# SwitchFeather.net
KiCad netlist of a schematic drawn in EAGLE
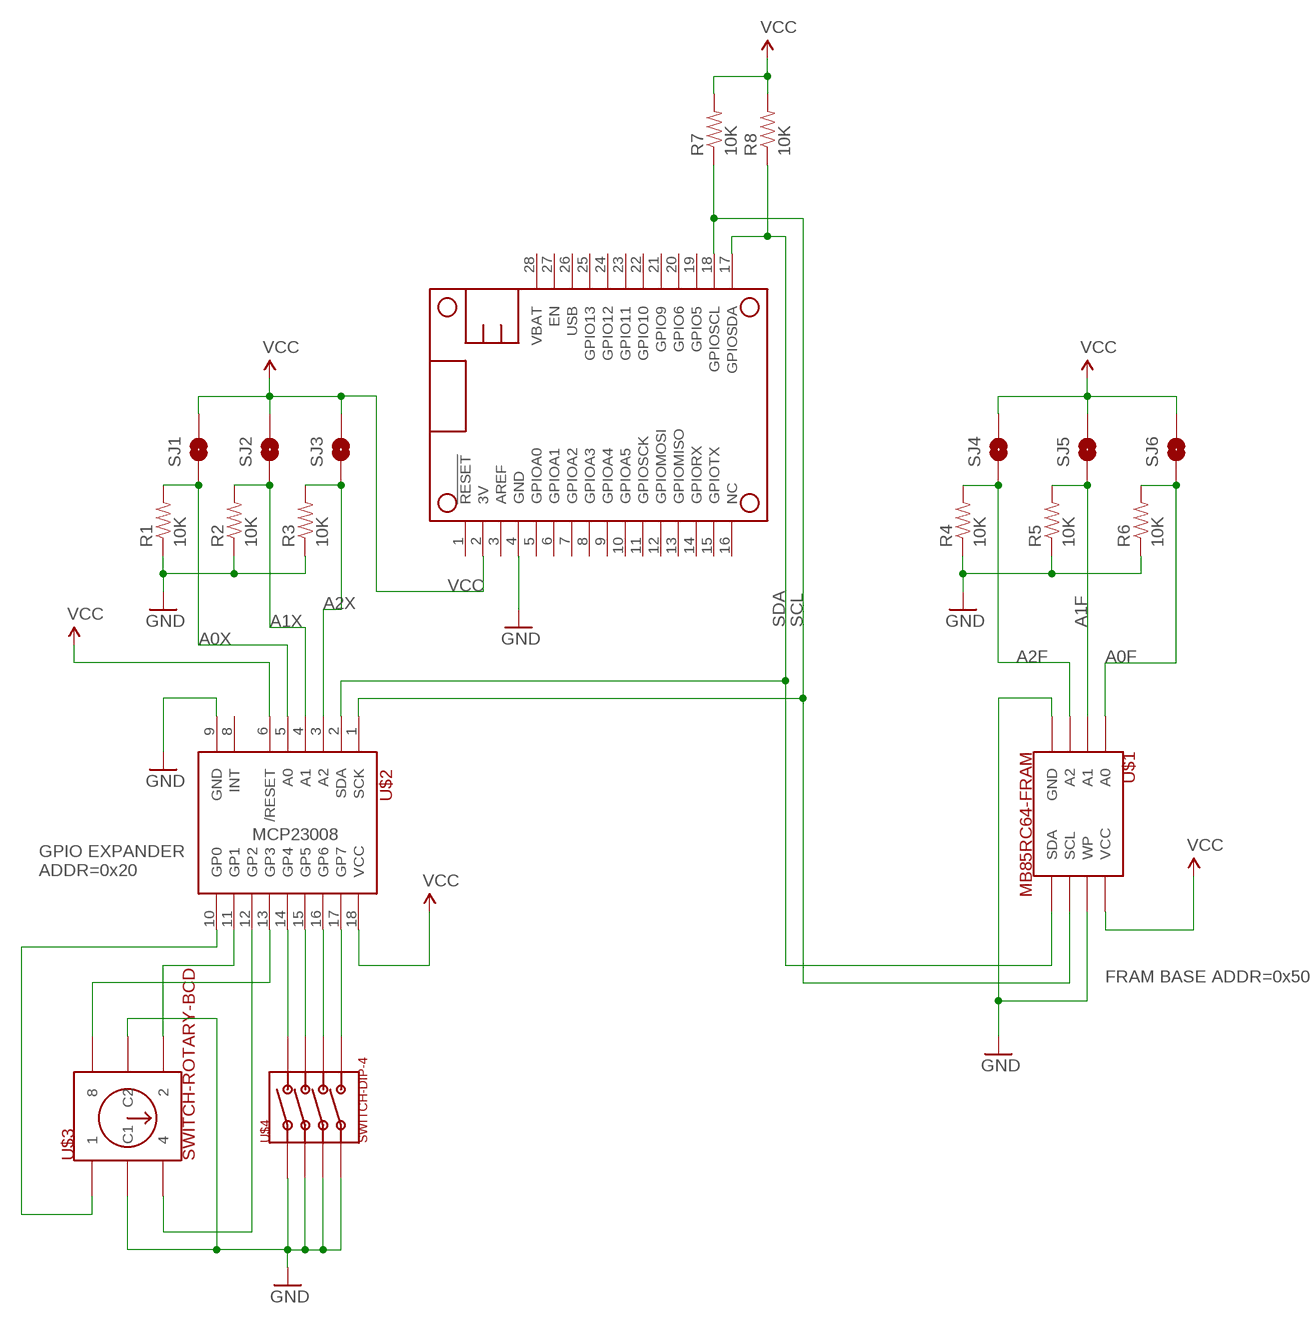
[diagram p0: schematic, sheet 1]

(export (version "E")
  (design (tool "Eeschema 10.0.6"))
  (components
    (comp (ref "MS1")
      (value "FEATHERWING")
      (footprint "eagle-import:FEATHERWING")
      (libsource (lib "eagle-import") (part "FEATHERWING"))
    )
    (comp (ref "R1")
      (value "10K")
      (footprint "eagle-import:0603-RES")
      (libsource (lib "eagle-import") (part "RES-10K-06030603"))
    )
    (comp (ref "R2")
      (value "10K")
      (footprint "eagle-import:0603-RES")
      (libsource (lib "eagle-import") (part "RES-10K-06030603"))
    )
    (comp (ref "R3")
      (value "10K")
      (footprint "eagle-import:0603-RES")
      (libsource (lib "eagle-import") (part "RES-10K-06030603"))
    )
    (comp (ref "R4")
      (value "10K")
      (footprint "eagle-import:0603-RES")
      (libsource (lib "eagle-import") (part "RES-10K-06030603"))
    )
    (comp (ref "R5")
      (value "10K")
      (footprint "eagle-import:0603-RES")
      (libsource (lib "eagle-import") (part "RES-10K-06030603"))
    )
    (comp (ref "R6")
      (value "10K")
      (footprint "eagle-import:0603-RES")
      (libsource (lib "eagle-import") (part "RES-10K-06030603"))
    )
    (comp (ref "R7")
      (value "10K")
      (footprint "eagle-import:0603-RES")
      (libsource (lib "eagle-import") (part "RES-10K-06030603"))
    )
    (comp (ref "R8")
      (value "10K")
      (footprint "eagle-import:0603-RES")
      (libsource (lib "eagle-import") (part "RES-10K-06030603"))
    )
    (comp (ref "SJ1")
      (value "JUMPER-PAD-2-NO")
      (footprint "eagle-import:PAD-JUMPER-2-NO_NO_SILK")
      (libsource (lib "eagle-import") (part "JUMPER-PAD-2-NO"))
    )
    (comp (ref "SJ2")
      (value "JUMPER-PAD-2-NO")
      (footprint "eagle-import:PAD-JUMPER-2-NO_NO_SILK")
      (libsource (lib "eagle-import") (part "JUMPER-PAD-2-NO"))
    )
    (comp (ref "SJ3")
      (value "JUMPER-PAD-2-NO")
      (footprint "eagle-import:PAD-JUMPER-2-NO_NO_SILK")
      (libsource (lib "eagle-import") (part "JUMPER-PAD-2-NO"))
    )
    (comp (ref "SJ4")
      (value "JUMPER-PAD-2-NO")
      (footprint "eagle-import:PAD-JUMPER-2-NO_NO_SILK")
      (libsource (lib "eagle-import") (part "JUMPER-PAD-2-NO"))
    )
    (comp (ref "SJ5")
      (value "JUMPER-PAD-2-NO")
      (footprint "eagle-import:PAD-JUMPER-2-NO_NO_SILK")
      (libsource (lib "eagle-import") (part "JUMPER-PAD-2-NO"))
    )
    (comp (ref "SJ6")
      (value "JUMPER-PAD-2-NO")
      (footprint "eagle-import:PAD-JUMPER-2-NO_NO_SILK")
      (libsource (lib "eagle-import") (part "JUMPER-PAD-2-NO"))
    )
    (comp (ref "U$1")
      (value "MB85RC64-FRAM")
      (footprint "eagle-import:8-SOIC-MAXIM")
      (libsource (lib "eagle-import") (part "MB85RC64-FRAM"))
    )
    (comp (ref "U$2")
      (value "MCP23008")
      (footprint "eagle-import:SOIC-18-W-MAXIM")
      (libsource (lib "eagle-import") (part "MCP23008"))
    )
    (comp (ref "U$3")
      (value "SWITCH-ROTARY-BCD")
      (footprint "eagle-import:SWITCH-ROTARY-BCD")
      (libsource (lib "eagle-import") (part "SWITCH-ROTARY-BCD"))
    )
    (comp (ref "U$4")
      (value "SWITCH-DIP-4")
      (footprint "eagle-import:SWITCH-DIP-4")
      (libsource (lib "eagle-import") (part "SWITCH-DIP-4"))
    )
  )
  (nets
    (net (code "1") (name "/A0F") (class "Default")
      (node (ref "R6") (pin "2") (pinfunction "2_2") (pintype "passive"))
      (node (ref "SJ6") (pin "1") (pinfunction "1_1") (pintype "passive"))
      (node (ref "U$1") (pin "1") (pinfunction "A0_1") (pintype "input"))
    )
    (net (code "2") (name "/A0X") (class "Default")
      (node (ref "R1") (pin "2") (pinfunction "2_2") (pintype "passive"))
      (node (ref "SJ1") (pin "1") (pinfunction "1_1") (pintype "passive"))
      (node (ref "U$2") (pin "5") (pinfunction "A0_5") (pintype "bidirectional"))
    )
    (net (code "3") (name "/A1F") (class "Default")
      (node (ref "R5") (pin "2") (pinfunction "2_2") (pintype "passive"))
      (node (ref "SJ5") (pin "1") (pinfunction "1_1") (pintype "passive"))
      (node (ref "U$1") (pin "2") (pinfunction "A1_2") (pintype "input"))
    )
    (net (code "4") (name "/A1X") (class "Default")
      (node (ref "R2") (pin "2") (pinfunction "2_2") (pintype "passive"))
      (node (ref "SJ2") (pin "1") (pinfunction "1_1") (pintype "passive"))
      (node (ref "U$2") (pin "4") (pinfunction "A1_4") (pintype "input"))
    )
    (net (code "5") (name "/A2F") (class "Default")
      (node (ref "R4") (pin "2") (pinfunction "2_2") (pintype "passive"))
      (node (ref "SJ4") (pin "1") (pinfunction "1_1") (pintype "passive"))
      (node (ref "U$1") (pin "3") (pinfunction "A2_3") (pintype "input"))
    )
    (net (code "6") (name "/A2X") (class "Default")
      (node (ref "R3") (pin "2") (pinfunction "2_2") (pintype "passive"))
      (node (ref "SJ3") (pin "1") (pinfunction "1_1") (pintype "passive"))
      (node (ref "U$2") (pin "3") (pinfunction "A2_3") (pintype "input"))
    )
    (net (code "7") (name "/SCL") (class "Default")
      (node (ref "MS1") (pin "18") (pinfunction "GPIOSCL_18") (pintype "bidirectional"))
      (node (ref "R7") (pin "1") (pinfunction "1_1") (pintype "passive"))
      (node (ref "U$1") (pin "6") (pinfunction "SCL_6") (pintype "input"))
      (node (ref "U$2") (pin "1") (pinfunction "SCK_1") (pintype "input"))
    )
    (net (code "8") (name "/SDA") (class "Default")
      (node (ref "MS1") (pin "17") (pinfunction "GPIOSDA_17") (pintype "bidirectional"))
      (node (ref "R8") (pin "1") (pinfunction "1_1") (pintype "passive"))
      (node (ref "U$1") (pin "5") (pinfunction "SDA_5") (pintype "bidirectional"))
      (node (ref "U$2") (pin "2") (pinfunction "SDA_2") (pintype "bidirectional"))
    )
    (net (code "9") (name "/USB") (class "Default")
      (node (ref "MS1") (pin "26") (pinfunction "USB_26") (pintype "power_in"))
    )
    (net (code "10") (name "/VBAT") (class "Default")
      (node (ref "MS1") (pin "28") (pinfunction "VBAT_28") (pintype "power_in"))
    )
    (net (code "11") (name "GND") (class "Default")
      (node (ref "MS1") (pin "4") (pinfunction "GND_4") (pintype "power_in"))
      (node (ref "R1") (pin "1") (pinfunction "1_1") (pintype "passive"))
      (node (ref "R2") (pin "1") (pinfunction "1_1") (pintype "passive"))
      (node (ref "R3") (pin "1") (pinfunction "1_1") (pintype "passive"))
      (node (ref "R4") (pin "1") (pinfunction "1_1") (pintype "passive"))
      (node (ref "R5") (pin "1") (pinfunction "1_1") (pintype "passive"))
      (node (ref "R6") (pin "1") (pinfunction "1_1") (pintype "passive"))
      (node (ref "U$1") (pin "4") (pinfunction "GND_4") (pintype "passive"))
      (node (ref "U$1") (pin "7") (pinfunction "WP_7") (pintype "input"))
      (node (ref "U$2") (pin "9") (pinfunction "GND_9") (pintype "passive"))
      (node (ref "U$3") (pin "P$2") (pinfunction "C1_P$2") (pintype "passive"))
      (node (ref "U$3") (pin "P$5") (pinfunction "C2_P$5") (pintype "passive"))
      (node (ref "U$4") (pin "P$1") (pinfunction "1_P$1") (pintype "passive"))
      (node (ref "U$4") (pin "P$3") (pinfunction "3_P$3") (pintype "passive"))
      (node (ref "U$4") (pin "P$5") (pinfunction "5_P$5") (pintype "passive"))
      (node (ref "U$4") (pin "P$7") (pinfunction "7_P$7") (pintype "passive"))
    )
    (net (code "12") (name "Net-(U$2-GP0)") (class "Default")
      (node (ref "U$2") (pin "10") (pinfunction "GP0_10") (pintype "bidirectional"))
      (node (ref "U$3") (pin "P$1") (pinfunction "1_P$1") (pintype "passive"))
    )
    (net (code "13") (name "Net-(U$2-GP1)") (class "Default")
      (node (ref "U$2") (pin "11") (pinfunction "GP1_11") (pintype "bidirectional"))
      (node (ref "U$3") (pin "P$4") (pinfunction "2_P$4") (pintype "passive"))
    )
    (net (code "14") (name "Net-(U$2-GP2)") (class "Default")
      (node (ref "U$2") (pin "12") (pinfunction "GP2_12") (pintype "bidirectional"))
      (node (ref "U$3") (pin "P$3") (pinfunction "4_P$3") (pintype "passive"))
    )
    (net (code "15") (name "Net-(U$2-GP3)") (class "Default")
      (node (ref "U$2") (pin "13") (pinfunction "GP3_13") (pintype "bidirectional"))
      (node (ref "U$3") (pin "P$6") (pinfunction "8_P$6") (pintype "passive"))
    )
    (net (code "16") (name "Net-(U$2-GP4)") (class "Default")
      (node (ref "U$2") (pin "14") (pinfunction "GP4_14") (pintype "bidirectional"))
      (node (ref "U$4") (pin "P$2") (pinfunction "2_P$2") (pintype "passive"))
    )
    (net (code "17") (name "Net-(U$2-GP5)") (class "Default")
      (node (ref "U$2") (pin "15") (pinfunction "GP5_15") (pintype "bidirectional"))
      (node (ref "U$4") (pin "P$4") (pinfunction "4_P$4") (pintype "passive"))
    )
    (net (code "18") (name "Net-(U$2-GP6)") (class "Default")
      (node (ref "U$2") (pin "16") (pinfunction "GP6_16") (pintype "bidirectional"))
      (node (ref "U$4") (pin "P$6") (pinfunction "6_P$6") (pintype "passive"))
    )
    (net (code "19") (name "Net-(U$2-GP7)") (class "Default")
      (node (ref "U$2") (pin "17") (pinfunction "GP7_17") (pintype "bidirectional"))
      (node (ref "U$4") (pin "P$8") (pinfunction "8_P$8") (pintype "passive"))
    )
    (net (code "20") (name "VCC") (class "Default")
      (node (ref "MS1") (pin "2") (pinfunction "3V_2") (pintype "power_in"))
      (node (ref "R7") (pin "2") (pinfunction "2_2") (pintype "passive"))
      (node (ref "R8") (pin "2") (pinfunction "2_2") (pintype "passive"))
      (node (ref "SJ1") (pin "2") (pinfunction "2_2") (pintype "passive"))
      (node (ref "SJ2") (pin "2") (pinfunction "2_2") (pintype "passive"))
      (node (ref "SJ3") (pin "2") (pinfunction "2_2") (pintype "passive"))
      (node (ref "SJ4") (pin "2") (pinfunction "2_2") (pintype "passive"))
      (node (ref "SJ5") (pin "2") (pinfunction "2_2") (pintype "passive"))
      (node (ref "SJ6") (pin "2") (pinfunction "2_2") (pintype "passive"))
      (node (ref "U$1") (pin "8") (pinfunction "VCC_8") (pintype "power_in"))
      (node (ref "U$2") (pin "18") (pinfunction "VCC_18") (pintype "passive"))
      (node (ref "U$2") (pin "6") (pinfunction "/RESET_6") (pintype "input"))
    )
    (net (code "21") (name "unconnected-(MS1-AREF-Pad3)") (class "Default")
      (node (ref "MS1") (pin "3") (pinfunction "AREF_3") (pintype "passive"))
    )
    (net (code "22") (name "unconnected-(MS1-EN-Pad27)") (class "Default")
      (node (ref "MS1") (pin "27") (pinfunction "EN_27") (pintype "passive"))
    )
    (net (code "23") (name "unconnected-(MS1-GPIO5-Pad19)") (class "Default")
      (node (ref "MS1") (pin "19") (pinfunction "GPIO5_19") (pintype "bidirectional"))
    )
    (net (code "24") (name "unconnected-(MS1-GPIO6-Pad20)") (class "Default")
      (node (ref "MS1") (pin "20") (pinfunction "GPIO6_20") (pintype "bidirectional"))
    )
    (net (code "25") (name "unconnected-(MS1-GPIO9-Pad21)") (class "Default")
      (node (ref "MS1") (pin "21") (pinfunction "GPIO9_21") (pintype "bidirectional"))
    )
    (net (code "26") (name "unconnected-(MS1-GPIO10-Pad22)") (class "Default")
      (node (ref "MS1") (pin "22") (pinfunction "GPIO10_22") (pintype "bidirectional"))
    )
    (net (code "27") (name "unconnected-(MS1-GPIO11-Pad23)") (class "Default")
      (node (ref "MS1") (pin "23") (pinfunction "GPIO11_23") (pintype "bidirectional"))
    )
    (net (code "28") (name "unconnected-(MS1-GPIO12-Pad24)") (class "Default")
      (node (ref "MS1") (pin "24") (pinfunction "GPIO12_24") (pintype "bidirectional"))
    )
    (net (code "29") (name "unconnected-(MS1-GPIO13-Pad25)") (class "Default")
      (node (ref "MS1") (pin "25") (pinfunction "GPIO13_25") (pintype "bidirectional"))
    )
    (net (code "30") (name "unconnected-(MS1-GPIOA0-Pad5)") (class "Default")
      (node (ref "MS1") (pin "5") (pinfunction "GPIOA0_5") (pintype "bidirectional"))
    )
    (net (code "31") (name "unconnected-(MS1-GPIOA1-Pad6)") (class "Default")
      (node (ref "MS1") (pin "6") (pinfunction "GPIOA1_6") (pintype "bidirectional"))
    )
    (net (code "32") (name "unconnected-(MS1-GPIOA2-Pad7)") (class "Default")
      (node (ref "MS1") (pin "7") (pinfunction "GPIOA2_7") (pintype "bidirectional"))
    )
    (net (code "33") (name "unconnected-(MS1-GPIOA3-Pad8)") (class "Default")
      (node (ref "MS1") (pin "8") (pinfunction "GPIOA3_8") (pintype "bidirectional"))
    )
    (net (code "34") (name "unconnected-(MS1-GPIOA4-Pad9)") (class "Default")
      (node (ref "MS1") (pin "9") (pinfunction "GPIOA4_9") (pintype "bidirectional"))
    )
    (net (code "35") (name "unconnected-(MS1-GPIOA5-Pad10)") (class "Default")
      (node (ref "MS1") (pin "10") (pinfunction "GPIOA5_10") (pintype "bidirectional"))
    )
    (net (code "36") (name "unconnected-(MS1-GPIOMISO-Pad13)") (class "Default")
      (node (ref "MS1") (pin "13") (pinfunction "GPIOMISO_13") (pintype "bidirectional"))
    )
    (net (code "37") (name "unconnected-(MS1-GPIOMOSI-Pad12)") (class "Default")
      (node (ref "MS1") (pin "12") (pinfunction "GPIOMOSI_12") (pintype "bidirectional"))
    )
    (net (code "38") (name "unconnected-(MS1-GPIORX-Pad14)") (class "Default")
      (node (ref "MS1") (pin "14") (pinfunction "GPIORX_14") (pintype "bidirectional"))
    )
    (net (code "39") (name "unconnected-(MS1-GPIOSCK-Pad11)") (class "Default")
      (node (ref "MS1") (pin "11") (pinfunction "GPIOSCK_11") (pintype "bidirectional"))
    )
    (net (code "40") (name "unconnected-(MS1-GPIOTX-Pad15)") (class "Default")
      (node (ref "MS1") (pin "15") (pinfunction "GPIOTX_15") (pintype "bidirectional"))
    )
    (net (code "41") (name "unconnected-(MS1-NC-Pad16)") (class "Default")
      (node (ref "MS1") (pin "16") (pinfunction "NC_16") (pintype "passive"))
    )
    (net (code "42") (name "unconnected-(MS1-~{RESET}-Pad1)") (class "Default")
      (node (ref "MS1") (pin "1") (pinfunction "~{RESET}_1") (pintype "input"))
    )
    (net (code "43") (name "unconnected-(U$2-INT-Pad8)") (class "Default")
      (node (ref "U$2") (pin "8") (pinfunction "INT_8") (pintype "output"))
    )
  )
)
